# 1_-_POWER.net
KiCad netlist of a schematic drawn in Altium Designer
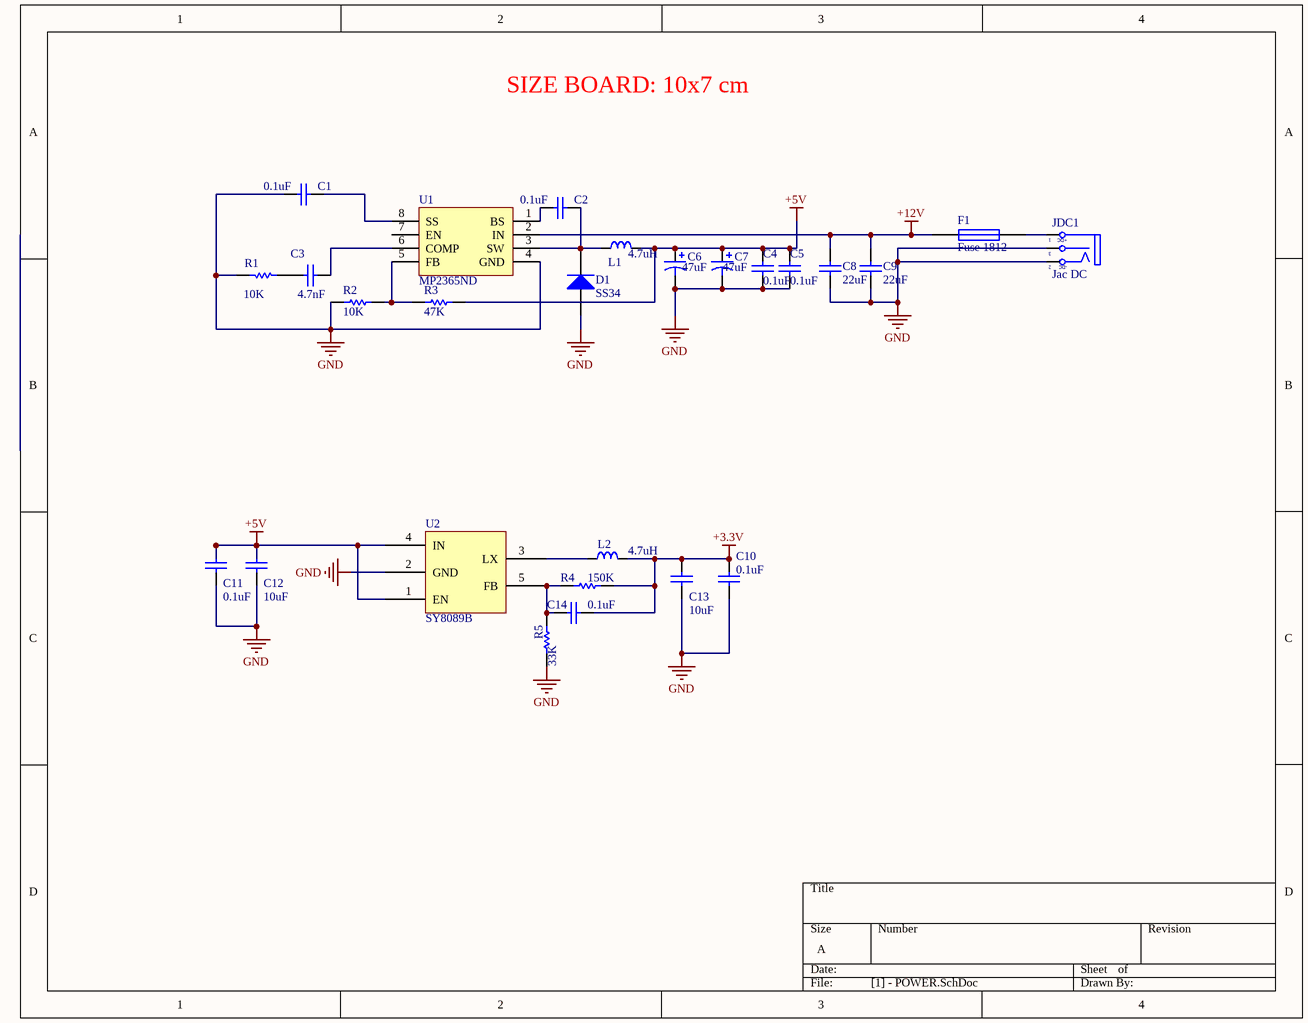
[diagram p0: [1] - POWER.SchDoc]

(export (version "E")
  (design (tool "Eeschema 10.0.6"))
  (components
    (comp (ref "C1")
      (value "0.1uF")
      (footprint "CN-SMD-0603")
      (description "CC0603KPX7R9BB104 0603 0.1 uF 50 V ±10% Tolerance X7R SMT Multilayer Ceramic Capacitor")
      (fields (field (name "TOLERANCE") "10%"))
      (libsource (lib "IOT_HIEP") (part "CN0603-0.1uF"))
    )
    (comp (ref "C2")
      (value "0.1uF")
      (footprint "CN-SMD-0603")
      (description "CC0603KPX7R9BB104 0603 0.1 uF 50 V ±10% Tolerance X7R SMT Multilayer Ceramic Capacitor")
      (fields (field (name "TOLERANCE") "10%"))
      (libsource (lib "IOT_HIEP") (part "CN0603-0.1uF"))
    )
    (comp (ref "C3")
      (value "4.7nF")
      (footprint "CN-SMD-0603")
      (description "CC0603KRX7R9BB472 Surface Mount Ceramic Multilayer Capacitor 0.0047uF 10% X7R 50V 0603 Paper T/R")
      (fields (field (name "TOLERANCE") "10%") (field (name "VOLTAGE") "50V"))
      (libsource (lib "IOT_HIEP") (part "CN0603-4.7nF"))
    )
    (comp (ref "C4")
      (value "0.1uF")
      (footprint "CN-SMD-0603")
      (description "CC0603KPX7R9BB104 0603 0.1 uF 50 V ±10% Tolerance X7R SMT Multilayer Ceramic Capacitor")
      (fields (field (name "TOLERANCE") "10%"))
      (libsource (lib "IOT_HIEP") (part "CN0603-0.1uF"))
    )
    (comp (ref "C5")
      (value "0.1uF")
      (footprint "CN-SMD-0603")
      (description "CC0603KPX7R9BB104 0603 0.1 uF 50 V ±10% Tolerance X7R SMT Multilayer Ceramic Capacitor")
      (fields (field (name "TOLERANCE") "10%"))
      (libsource (lib "IOT_HIEP") (part "CN0603-0.1uF"))
    )
    (comp (ref "C6")
      (value "47uF")
      (footprint "Cap size C")
      (description "TPSC476M016R0350 CAP TANT 47UF 16V 20% 2312")
      (fields (field (name "TOLERANCE") "20%") (field (name "VOLTAGE") "16V"))
      (libsource (lib "IOT_HIEP") (part "CN6032-47uF"))
    )
    (comp (ref "C7")
      (value "47uF")
      (footprint "Cap size C")
      (description "TPSC476M016R0350 CAP TANT 47UF 16V 20% 2312")
      (fields (field (name "TOLERANCE") "20%") (field (name "VOLTAGE") "16V"))
      (libsource (lib "IOT_HIEP") (part "CN6032-47uF"))
    )
    (comp (ref "C8")
      (value "22uF")
      (footprint "CN-SMD-0805")
      (description "CC0805MKX5R6BB226 0805 22 uF 10 V ±20 % Tolerance X5R SMT Multilayer Ceramic Capacitor")
      (fields (field (name "TOLERANCE") "20%"))
      (libsource (lib "IOT_HIEP") (part "CN0805-22uF"))
    )
    (comp (ref "C9")
      (value "22uF")
      (footprint "CN-SMD-0805")
      (description "CC0805MKX5R6BB226 0805 22 uF 10 V ±20 % Tolerance X5R SMT Multilayer Ceramic Capacitor")
      (fields (field (name "TOLERANCE") "20%"))
      (libsource (lib "IOT_HIEP") (part "CN0805-22uF"))
    )
    (comp (ref "C10")
      (value "0.1uF")
      (footprint "CN-SMD-0603")
      (description "CC0603KPX7R9BB104 0603 0.1 uF 50 V ±10% Tolerance X7R SMT Multilayer Ceramic Capacitor")
      (fields (field (name "TOLERANCE") "10%"))
      (libsource (lib "IOT_HIEP") (part "CN0603-0.1uF"))
    )
    (comp (ref "C11")
      (value "0.1uF")
      (footprint "CN-SMD-0603")
      (description "CC0603KPX7R9BB104 0603 0.1 uF 50 V ±10% Tolerance X7R SMT Multilayer Ceramic Capacitor")
      (fields (field (name "TOLERANCE") "10%"))
      (libsource (lib "IOT_HIEP") (part "CN0603-0.1uF"))
    )
    (comp (ref "C12")
      (value "10uF")
      (footprint "CN-SMD-0805")
      (description "CC0805KKX5R8BB106 0805 10 uF 25 V ±10 % Tolerance X5R SMT Multilayer Ceramic Capacitor")
      (fields (field (name "TOLERANCE") "10%"))
      (libsource (lib "IOT_HIEP") (part "CN0805_10uF"))
    )
    (comp (ref "C13")
      (value "10uF")
      (footprint "CN-SMD-0805")
      (description "CC0805KKX5R8BB106 0805 10 uF 25 V ±10 % Tolerance X5R SMT Multilayer Ceramic Capacitor")
      (fields (field (name "TOLERANCE") "10%"))
      (libsource (lib "IOT_HIEP") (part "CN0805_10uF"))
    )
    (comp (ref "C14")
      (value "0.1uF")
      (footprint "CN-SMD-0603")
      (description "CC0603KPX7R9BB104 0603 0.1 uF 50 V ±10% Tolerance X7R SMT Multilayer Ceramic Capacitor")
      (fields (field (name "TOLERANCE") "10%"))
      (libsource (lib "IOT_HIEP") (part "CN0603-0.1uF"))
    )
    (comp (ref "D1")
      (value "SS34")
      (footprint "DO-214AC")
      (description "SS34 DIODE SCHOTTKY 40V 3A SMC")
      (fields (field (name "VOLTAGE") "40V"))
      (libsource (lib "IOT_HIEP") (part "Diode_SS34"))
    )
    (comp (ref "F1")
      (value "Fuse 1812")
      (footprint "fuse_1812")
      (description "Fuse")
      (fields
        (field (name "MANUFACTURER") "Littelfuse")
        (field (name "MANUFACTURER PART NUMBER") "MINISMDC150F/24-2")
      )
      (libsource (lib "NestHouse") (part "Fuse 1"))
    )
    (comp (ref "JDC1")
      (value "Jac DC")
      (footprint "DC0")
      (description "Jac DC input")
      (libsource (lib "THUVIENTUTAO") (part "DCIN_1"))
    )
    (comp (ref "L1")
      (value "4.7uH")
      (footprint "INDUCTOR CD75")
      (description "CDRH5D28RHPNP-4R7NC Fixed Inductors 4.7uH 3.05A")
      (fields (field (name "TOLERANCE") "25%"))
      (libsource (lib "IOT_HIEP") (part "L-4.7uH"))
    )
    (comp (ref "L2")
      (value "4.7uH")
      (footprint "INDUCTOR CD75")
      (description "CDRH5D28RHPNP-4R7NC Fixed Inductors 4.7uH 3.05A")
      (fields (field (name "TOLERANCE") "25%"))
      (libsource (lib "") (part "L-4.7uH_1"))
    )
    (comp (ref "R1")
      (value "10K")
      (footprint "RES 0603")
      (description "AC0603FR-0710KL Res Thick Film 0603 10K Ohm 1% 0.1W(1/10W) ±100ppm/C Pad SMD Automotive T/R")
      (fields (field (name "TOLERANCE") "1%"))
      (libsource (lib "IOT_HIEP") (part "RC0603_10K"))
    )
    (comp (ref "R2")
      (value "10K")
      (footprint "RES 0603")
      (description "AC0603FR-0710KL Res Thick Film 0603 10K Ohm 1% 0.1W(1/10W) ±100ppm/C Pad SMD Automotive T/R")
      (fields (field (name "TOLERANCE") "1%"))
      (libsource (lib "IOT_HIEP") (part "RC0603_10K"))
    )
    (comp (ref "R3")
      (value "47K")
      (footprint "RES 0603")
      (description "AC0603JR-0747KL Res Thick Film 0603 47K Ohm 5% 0.1W(1/10W) +/-100ppm/ßC Epoxy SMD Automotive T/R")
      (fields (field (name "TOLERANCE") "5%"))
      (libsource (lib "IOT_HIEP") (part "RC0603_47K"))
    )
    (comp (ref "R4")
      (value "150K")
      (footprint "RES 0603")
      (fields (field (name "TOLERANCE") "5%"))
      (libsource (lib "IOT_HIEP") (part "RC0603_150K"))
    )
    (comp (ref "R5")
      (value "33K")
      (footprint "RES 0603")
      (description "AC0603JR-0733KL Res Thick Film 0603 33K Ohm 5% 0.1W(1/10W) ±100ppm/C Pad SMD Automotive T/R")
      (fields (field (name "TOLERANCE") "5%"))
      (libsource (lib "IOT_HIEP") (part "RC0603_33K"))
    )
    (comp (ref "U1")
      (value "MP2365ND")
      (footprint "MP2365ND")
      (fields
        (field (name "MANUFACTURER") "Monolithic Power Systems")
        (field (name "MANUFACTURER PART NUMBER") "MP2365DN-LF-Z")
      )
      (libsource (lib "NestHouse") (part "Switching MP2365ND"))
    )
    (comp (ref "U2")
      (value "SY8089B")
      (footprint "SOT23-5")
      (description "High Efficiency 5.5V, 2A continuous, 3A peak, 1MHz  Synchronous Step Down Regulator")
      (fields (field (name "MANUFACTURER") "Silergy") (field (name "MANUFACTURER PART NUMBER") "SY8089A"))
      (libsource (lib "NestHouse") (part "SY8089B"))
    )
  )
  (nets
    (net (code "1") (name "+3.3V") (class "Default")
      (node (ref "C10") (pin "1") (pinfunction "1_1") (pintype "passive"))
      (node (ref "C13") (pin "2") (pinfunction "2_2") (pintype "passive"))
      (node (ref "C14") (pin "1") (pinfunction "1_1") (pintype "passive"))
      (node (ref "L2") (pin "2") (pinfunction "2_2") (pintype "passive"))
      (node (ref "R4") (pin "1") (pinfunction "1_1") (pintype "passive"))
    )
    (net (code "2") (name "+5V") (class "Default")
      (node (ref "C11") (pin "2") (pinfunction "2_2") (pintype "passive"))
      (node (ref "C12") (pin "2") (pinfunction "2_2") (pintype "passive"))
      (node (ref "C4") (pin "2") (pinfunction "2_2") (pintype "passive"))
      (node (ref "C5") (pin "2") (pinfunction "2_2") (pintype "passive"))
      (node (ref "C6") (pin "1") (pinfunction "1_1") (pintype "passive"))
      (node (ref "C7") (pin "1") (pinfunction "1_1") (pintype "passive"))
      (node (ref "L1") (pin "1") (pinfunction "1_1") (pintype "passive"))
      (node (ref "R3") (pin "2") (pinfunction "2_2") (pintype "passive"))
      (node (ref "U2") (pin "1") (pinfunction "EN_1") (pintype "passive"))
      (node (ref "U2") (pin "4") (pinfunction "IN_4") (pintype "passive"))
    )
    (net (code "3") (name "+12V") (class "Default")
      (node (ref "C8") (pin "1") (pinfunction "1_1") (pintype "passive"))
      (node (ref "C9") (pin "2") (pinfunction "2_2") (pintype "passive"))
      (node (ref "F1") (pin "1") (pinfunction "1_1") (pintype "passive"))
      (node (ref "U1") (pin "2") (pinfunction "IN_2") (pintype "passive"))
    )
    (net (code "4") (name "GND") (class "Default")
      (node (ref "C1") (pin "1") (pinfunction "1_1") (pintype "passive"))
      (node (ref "C10") (pin "2") (pinfunction "2_2") (pintype "passive"))
      (node (ref "C11") (pin "1") (pinfunction "1_1") (pintype "passive"))
      (node (ref "C12") (pin "1") (pinfunction "1_1") (pintype "passive"))
      (node (ref "C13") (pin "1") (pinfunction "1_1") (pintype "passive"))
      (node (ref "C4") (pin "1") (pinfunction "1_1") (pintype "passive"))
      (node (ref "C5") (pin "1") (pinfunction "1_1") (pintype "passive"))
      (node (ref "C6") (pin "2") (pinfunction "2_2") (pintype "passive"))
      (node (ref "C7") (pin "2") (pinfunction "2_2") (pintype "passive"))
      (node (ref "C8") (pin "2") (pinfunction "2_2") (pintype "passive"))
      (node (ref "C9") (pin "1") (pinfunction "1_1") (pintype "passive"))
      (node (ref "D1") (pin "1") (pinfunction "A_1") (pintype "passive"))
      (node (ref "JDC1") (pin "2") (pinfunction "TN_2") (pintype "passive"))
      (node (ref "JDC1") (pin "3") (pinfunction "S_3") (pintype "power_in"))
      (node (ref "R1") (pin "2") (pinfunction "2_2") (pintype "passive"))
      (node (ref "R2") (pin "1") (pinfunction "1_1") (pintype "passive"))
      (node (ref "R5") (pin "1") (pinfunction "1_1") (pintype "passive"))
      (node (ref "U1") (pin "4") (pinfunction "GND_4") (pintype "passive"))
      (node (ref "U2") (pin "2") (pinfunction "GND_2") (pintype "passive"))
    )
    (net (code "5") (name "Net-(C3-Pad1)") (class "Default")
      (node (ref "C3") (pin "1") (pinfunction "1_1") (pintype "passive"))
      (node (ref "R1") (pin "1") (pinfunction "1_1") (pintype "passive"))
    )
    (net (code "6") (name "Net-(D1-K)") (class "Default")
      (node (ref "C2") (pin "2") (pinfunction "2_2") (pintype "passive"))
      (node (ref "D1") (pin "2") (pinfunction "K_2") (pintype "passive"))
      (node (ref "L1") (pin "2") (pinfunction "2_2") (pintype "passive"))
      (node (ref "U1") (pin "3") (pinfunction "SW_3") (pintype "passive"))
    )
    (net (code "7") (name "Net-(JDC1-T)") (class "Default")
      (node (ref "F1") (pin "2") (pinfunction "2_2") (pintype "passive"))
      (node (ref "JDC1") (pin "1") (pinfunction "T_1") (pintype "passive"))
    )
    (net (code "8") (name "Net-(U1-BS)") (class "Default")
      (node (ref "C2") (pin "1") (pinfunction "1_1") (pintype "passive"))
      (node (ref "U1") (pin "1") (pinfunction "BS_1") (pintype "passive"))
    )
    (net (code "9") (name "Net-(U1-COMP)") (class "Default")
      (node (ref "C3") (pin "2") (pinfunction "2_2") (pintype "passive"))
      (node (ref "U1") (pin "6") (pinfunction "COMP_6") (pintype "passive"))
    )
    (net (code "10") (name "Net-(U1-FB)") (class "Default")
      (node (ref "R2") (pin "2") (pinfunction "2_2") (pintype "passive"))
      (node (ref "R3") (pin "1") (pinfunction "1_1") (pintype "passive"))
      (node (ref "U1") (pin "5") (pinfunction "FB_5") (pintype "passive"))
    )
    (net (code "11") (name "Net-(U1-SS)") (class "Default")
      (node (ref "C1") (pin "2") (pinfunction "2_2") (pintype "passive"))
      (node (ref "U1") (pin "8") (pinfunction "SS_8") (pintype "passive"))
    )
    (net (code "12") (name "Net-(U2-FB)") (class "Default")
      (node (ref "C14") (pin "2") (pinfunction "2_2") (pintype "passive"))
      (node (ref "R4") (pin "2") (pinfunction "2_2") (pintype "passive"))
      (node (ref "R5") (pin "2") (pinfunction "2_2") (pintype "passive"))
      (node (ref "U2") (pin "5") (pinfunction "FB_5") (pintype "passive"))
    )
    (net (code "13") (name "Net-(U2-LX)") (class "Default")
      (node (ref "L2") (pin "1") (pinfunction "1_1") (pintype "passive"))
      (node (ref "U2") (pin "3") (pinfunction "LX_3") (pintype "passive"))
    )
    (net (code "14") (name "unconnected-(U1-EN-Pad7)") (class "Default")
      (node (ref "U1") (pin "7") (pinfunction "EN_7") (pintype "passive"))
    )
  )
)
